# Adapter.net
KiCad netlist of a schematic drawn in Altium Designer
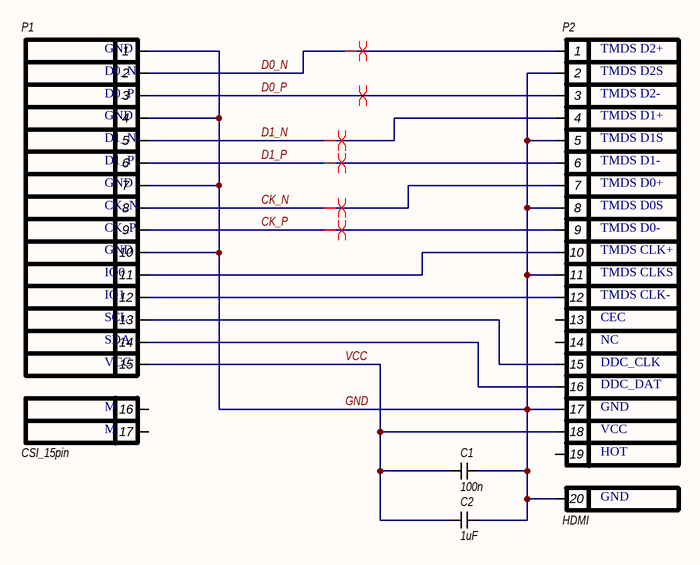
[diagram p0: Adapter.SchDoc]

(export (version "E")
  (design (tool "Eeschema 10.0.6"))
  (components
    (comp (ref "C1") (value "100n") (footprint "CAP_0603") (libsource (lib "Common") (part "Capacitor")))
    (comp (ref "C2") (value "1uF") (footprint "CAP_0603") (libsource (lib "Common") (part "Capacitor")))
    (comp (ref "P1")
      (value "CSI_15pin")
      (footprint "FDC CSI 15pin")
      (libsource (lib "Connectors") (part "Port 17"))
    )
    (comp (ref "P2") (value "HDMI") (footprint "HDMI TYPE A") (libsource (lib "Connectors") (part "Port 20")))
  )
  (nets
    (net (code "1") (name "/CK_N") (class "Default")
      (node (ref "P1") (pin "8") (pinfunction "8_8") (pintype "passive"))
      (node (ref "P2") (pin "7") (pinfunction "7_7") (pintype "passive"))
    )
    (net (code "2") (name "/CK_P") (class "Default")
      (node (ref "P1") (pin "9") (pinfunction "9_9") (pintype "passive"))
      (node (ref "P2") (pin "9") (pinfunction "9_9") (pintype "passive"))
    )
    (net (code "3") (name "/D0_N") (class "Default")
      (node (ref "P1") (pin "2") (pinfunction "2_2") (pintype "passive"))
      (node (ref "P2") (pin "1") (pinfunction "1_1") (pintype "passive"))
    )
    (net (code "4") (name "/D0_P") (class "Default")
      (node (ref "P1") (pin "3") (pinfunction "3_3") (pintype "passive"))
      (node (ref "P2") (pin "3") (pinfunction "3_3") (pintype "passive"))
    )
    (net (code "5") (name "/D1_N") (class "Default")
      (node (ref "P1") (pin "5") (pinfunction "5_5") (pintype "passive"))
      (node (ref "P2") (pin "4") (pinfunction "4_4") (pintype "passive"))
    )
    (net (code "6") (name "/D1_P") (class "Default")
      (node (ref "P1") (pin "6") (pinfunction "6_6") (pintype "passive"))
      (node (ref "P2") (pin "6") (pinfunction "6_6") (pintype "passive"))
    )
    (net (code "7") (name "/GND") (class "Default")
      (node (ref "C1") (pin "2") (pinfunction "2_2") (pintype "passive"))
      (node (ref "C2") (pin "2") (pinfunction "2_2") (pintype "passive"))
      (node (ref "P1") (pin "1") (pinfunction "1_1") (pintype "passive"))
      (node (ref "P1") (pin "10") (pinfunction "10_10") (pintype "passive"))
      (node (ref "P1") (pin "4") (pinfunction "4_4") (pintype "passive"))
      (node (ref "P1") (pin "7") (pinfunction "7_7") (pintype "passive"))
      (node (ref "P2") (pin "11") (pinfunction "11_11") (pintype "passive"))
      (node (ref "P2") (pin "17") (pinfunction "17_17") (pintype "passive"))
      (node (ref "P2") (pin "2") (pinfunction "2_2") (pintype "passive"))
      (node (ref "P2") (pin "20") (pinfunction "20_20") (pintype "passive"))
      (node (ref "P2") (pin "5") (pinfunction "5_5") (pintype "passive"))
      (node (ref "P2") (pin "8") (pinfunction "8_8") (pintype "passive"))
    )
    (net (code "8") (name "/VCC") (class "Default")
      (node (ref "C1") (pin "1") (pinfunction "1_1") (pintype "passive"))
      (node (ref "C2") (pin "1") (pinfunction "1_1") (pintype "passive"))
      (node (ref "P1") (pin "15") (pinfunction "15_15") (pintype "passive"))
      (node (ref "P2") (pin "18") (pinfunction "18_18") (pintype "passive"))
    )
    (net (code "9") (name "Net-(P1-Pad11)") (class "Default")
      (node (ref "P1") (pin "11") (pinfunction "11_11") (pintype "passive"))
      (node (ref "P2") (pin "10") (pinfunction "10_10") (pintype "passive"))
    )
    (net (code "10") (name "Net-(P1-Pad12)") (class "Default")
      (node (ref "P1") (pin "12") (pinfunction "12_12") (pintype "passive"))
      (node (ref "P2") (pin "12") (pinfunction "12_12") (pintype "passive"))
    )
    (net (code "11") (name "Net-(P1-Pad13)") (class "Default")
      (node (ref "P1") (pin "13") (pinfunction "13_13") (pintype "passive"))
      (node (ref "P2") (pin "15") (pinfunction "15_15") (pintype "passive"))
    )
    (net (code "12") (name "Net-(P1-Pad14)") (class "Default")
      (node (ref "P1") (pin "14") (pinfunction "14_14") (pintype "passive"))
      (node (ref "P2") (pin "16") (pinfunction "16_16") (pintype "passive"))
    )
    (net (code "13") (name "unconnected-(P1-Pad16)") (class "Default")
      (node (ref "P1") (pin "16") (pinfunction "16_16") (pintype "passive"))
    )
    (net (code "14") (name "unconnected-(P1-Pad17)") (class "Default")
      (node (ref "P1") (pin "17") (pinfunction "17_17") (pintype "passive"))
    )
    (net (code "15") (name "unconnected-(P2-Pad13)") (class "Default")
      (node (ref "P2") (pin "13") (pinfunction "13_13") (pintype "passive"))
    )
    (net (code "16") (name "unconnected-(P2-Pad14)") (class "Default")
      (node (ref "P2") (pin "14") (pinfunction "14_14") (pintype "passive"))
    )
    (net (code "17") (name "unconnected-(P2-Pad19)") (class "Default")
      (node (ref "P2") (pin "19") (pinfunction "19_19") (pintype "passive"))
    )
  )
)
